# Power.net
KiCad netlist of a schematic drawn in Altium Designer
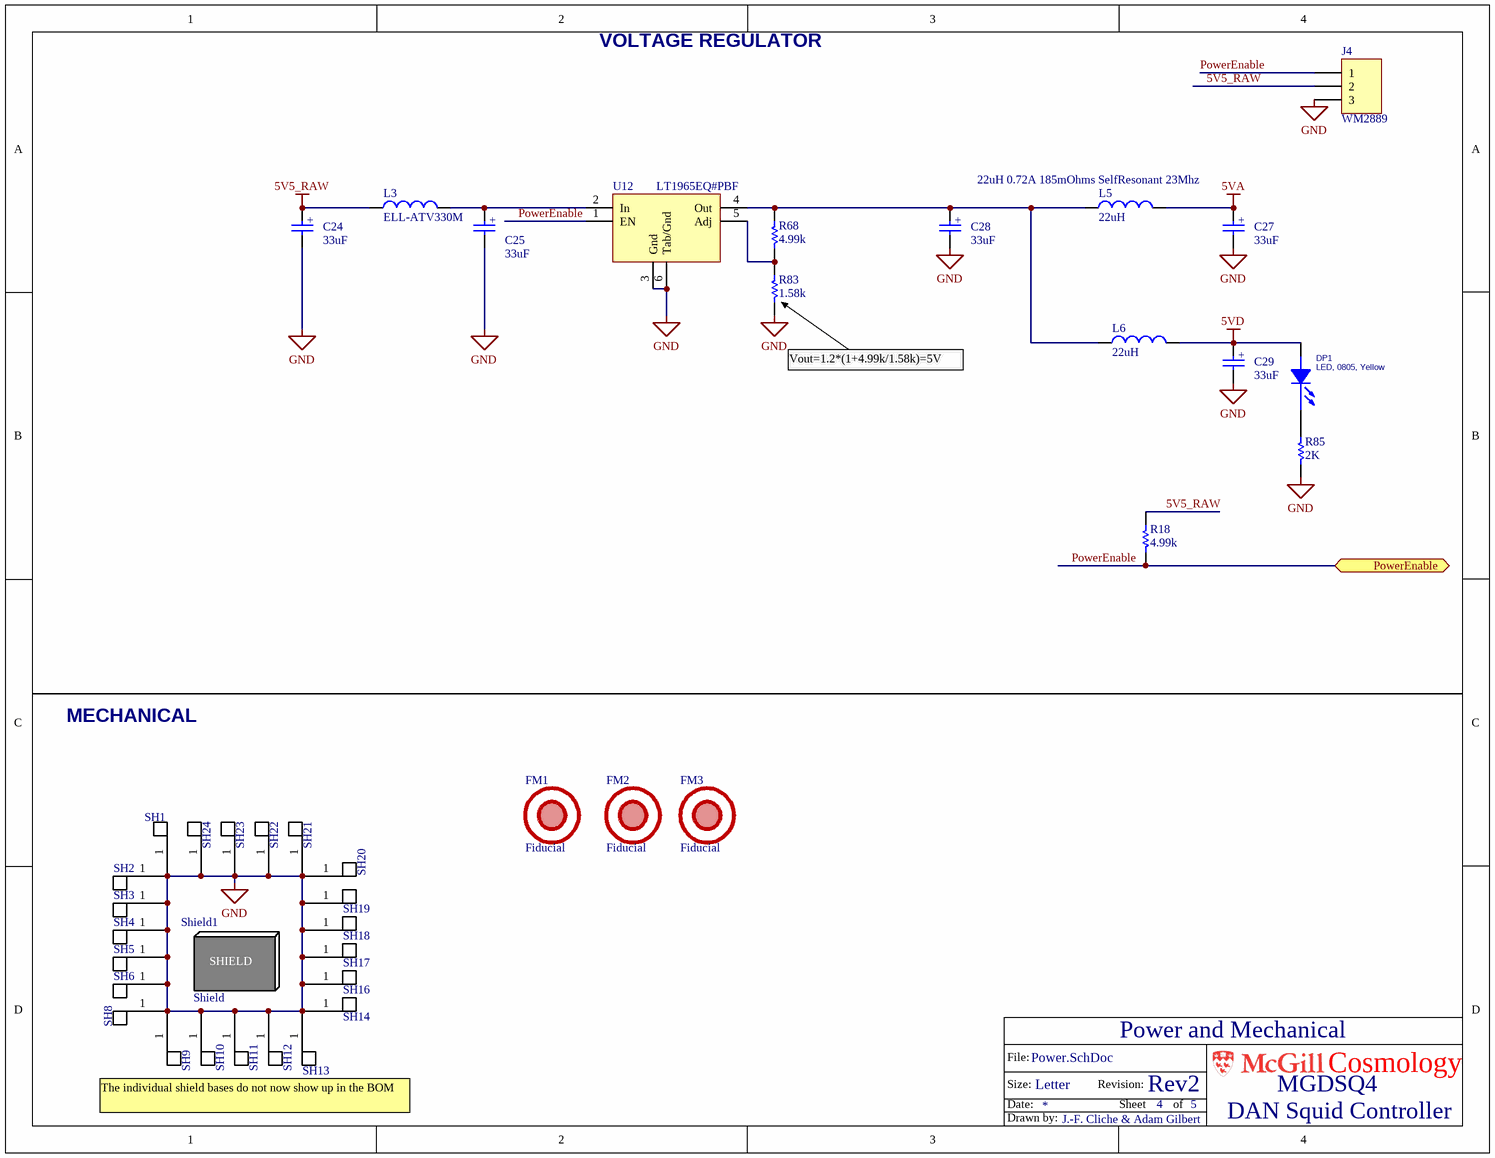
[diagram p0: Power.SchDoc]

(export (version "E")
  (design (tool "Eeschema 10.0.6"))
  (components
    (comp (ref "C24")
      (value "33uF")
      (footprint "TCASE-D")
      (description "CAP TANT CASE-D")
      (fields (field (name "VOLTAGE") "16V") (field (name "MANUFACTURER") "Generic"))
      (libsource (lib "MiniSquidCtrl") (part "Tantalum"))
    )
    (comp (ref "C25")
      (value "33uF")
      (footprint "TCASE-D")
      (description "CAP TANT CASE-D")
      (fields (field (name "VOLTAGE") "16V") (field (name "MANUFACTURER") "Generic"))
      (libsource (lib "MiniSquidCtrl") (part "Tantalum"))
    )
    (comp (ref "C27")
      (value "33uF")
      (footprint "TCASE-D")
      (description "CAP TANT CASE-D")
      (fields (field (name "VOLTAGE") "16V") (field (name "MANUFACTURER") "Generic"))
      (libsource (lib "MiniSquidCtrl") (part "Tantalum"))
    )
    (comp (ref "C28")
      (value "33uF")
      (footprint "TCASE-D")
      (description "CAP TANT CASE-D")
      (fields (field (name "VOLTAGE") "16V") (field (name "MANUFACTURER") "Generic"))
      (libsource (lib "MiniSquidCtrl") (part "Tantalum"))
    )
    (comp (ref "C29")
      (value "33uF")
      (footprint "TCASE-D")
      (description "CAP TANT CASE-D")
      (fields (field (name "VOLTAGE") "16V") (field (name "MANUFACTURER") "Generic"))
      (libsource (lib "MiniSquidCtrl") (part "Tantalum"))
    )
    (comp (ref "DP1")
      (value "LED, 0805, Yellow")
      (description "LED")
      (libsource (lib "MiniSquidCtrl") (part "LED, yellow, 0805, 2mA"))
    )
    (comp (ref "FM1")
      (value "Fiducial")
      (footprint "Fiducial_mark")
      (libsource (lib "MiniSquidCtrl") (part "Fiducial"))
    )
    (comp (ref "FM2")
      (value "Fiducial")
      (footprint "Fiducial_mark")
      (libsource (lib "MiniSquidCtrl") (part "Fiducial"))
    )
    (comp (ref "FM3")
      (value "Fiducial")
      (footprint "Fiducial_mark")
      (libsource (lib "MiniSquidCtrl") (part "Fiducial"))
    )
    (comp (ref "J4")
      (value "WM2889")
      (footprint "HDR1X3_MolexVertical")
      (description "3-Pin 0.1\" header")
      (fields (field (name "MANUFACTURER") "Digikey"))
      (libsource (lib "MiniSquidCtrl") (part "Header 3"))
    )
    (comp (ref "L3")
      (value "ELL-ATV330M")
      (footprint "ELLATV")
      (description "33uH 1.8A inductor 10mmx10mm")
      (fields (field (name "MANUFACTURER") "Panasonic - ECG") (field (name "TOLERANCE") "±20%"))
      (libsource (lib "MiniSquidCtrl") (part "ELL-ATV330M"))
    )
    (comp (ref "L5")
      (value "22uH")
      (footprint "SRR4028")
      (description "=PartConstraints")
      (fields
        (field (name "MANUFACTURER") "Bourns")
        (field (name "PARTCONSTRAINTS") "22uH 0.72A 185mOhms SelfResonant 23Mhz")
      )
      (libsource (lib "MiniSquidCtrl") (part "InductorSRR4028"))
    )
    (comp (ref "L6")
      (value "22uH")
      (footprint "SRR4028")
      (description "=PartConstraints")
      (fields (field (name "MANUFACTURER") "Bourns"))
      (libsource (lib "MiniSquidCtrl") (part "InductorSRR4028"))
    )
    (comp (ref "R18")
      (value "4.99k")
      (footprint "0603")
      (description "RES 0603")
      (fields (field (name "MANUFACTURER") "Generic"))
      (libsource (lib "MiniSquidCtrl") (part "Res0603"))
    )
    (comp (ref "R68")
      (value "4.99k")
      (footprint "0603")
      (description "RES 0603")
      (fields (field (name "MANUFACTURER") "Generic"))
      (libsource (lib "MiniSquidCtrl") (part "Res0603"))
    )
    (comp (ref "R83")
      (value "1.58k")
      (footprint "0603")
      (description "RES 0603")
      (fields (field (name "MANUFACTURER") "Generic"))
      (libsource (lib "MiniSquidCtrl") (part "Res0603"))
    )
    (comp (ref "R85")
      (value "2K")
      (footprint "0603")
      (description "RES 0603")
      (fields (field (name "MANUFACTURER") "Generic") (field (name "Comment") "2k"))
      (libsource (lib "MiniSquidCtrl") (part "Res0603"))
    )
    (comp (ref "SH1")
      (value "LeaderTech 20S-CBS-2x0.5x0.2 - DIVIDE QUANITY REQURIED BY 10!")
      (footprint "SHIELD BASE CORNER")
      (fields (field (name "MANUFACTURER") "LeaderTech"))
      (libsource (lib "MiniSquidCtrl") (part "ShieldBase"))
    )
    (comp (ref "SH2")
      (value "LeaderTech 20S-CBS-2x0.5x0.2 - DIVIDE QUANITY REQURIED BY 10!")
      (footprint "SHIELD BASE")
      (fields (field (name "MANUFACTURER") "LeaderTech"))
      (libsource (lib "MiniSquidCtrl") (part "ShieldBase"))
    )
    (comp (ref "SH3")
      (value "LeaderTech 20S-CBS-2x0.5x0.2 - DIVIDE QUANITY REQURIED BY 10!")
      (footprint "SHIELD BASE")
      (fields (field (name "MANUFACTURER") "LeaderTech"))
      (libsource (lib "MiniSquidCtrl") (part "ShieldBase"))
    )
    (comp (ref "SH4")
      (value "LeaderTech 20S-CBS-2x0.5x0.2 - DIVIDE QUANITY REQURIED BY 10!")
      (footprint "SHIELD BASE")
      (fields (field (name "MANUFACTURER") "LeaderTech"))
      (libsource (lib "MiniSquidCtrl") (part "ShieldBase"))
    )
    (comp (ref "SH5")
      (value "LeaderTech 20S-CBS-2x0.5x0.2 - DIVIDE QUANITY REQURIED BY 10!")
      (footprint "SHIELD BASE")
      (fields (field (name "MANUFACTURER") "LeaderTech"))
      (libsource (lib "MiniSquidCtrl") (part "ShieldBase"))
    )
    (comp (ref "SH6")
      (value "LeaderTech 20S-CBS-2x0.5x0.2 - DIVIDE QUANITY REQURIED BY 10!")
      (footprint "SHIELD BASE")
      (fields (field (name "MANUFACTURER") "LeaderTech"))
      (libsource (lib "MiniSquidCtrl") (part "ShieldBase"))
    )
    (comp (ref "SH8")
      (value "LeaderTech 20S-CBS-2x0.5x0.2 - DIVIDE QUANITY REQURIED BY 10!")
      (footprint "SHIELD BASE CORNER")
      (fields (field (name "MANUFACTURER") "LeaderTech"))
      (libsource (lib "MiniSquidCtrl") (part "ShieldBase"))
    )
    (comp (ref "SH9")
      (value "LeaderTech 20S-CBS-2x0.5x0.2 - DIVIDE QUANITY REQURIED BY 10!")
      (footprint "SHIELD BASE")
      (fields (field (name "MANUFACTURER") "LeaderTech"))
      (libsource (lib "MiniSquidCtrl") (part "ShieldBase"))
    )
    (comp (ref "SH10")
      (value "LeaderTech 20S-CBS-2x0.5x0.2 - DIVIDE QUANITY REQURIED BY 10!")
      (footprint "SHIELD BASE")
      (fields (field (name "MANUFACTURER") "LeaderTech"))
      (libsource (lib "MiniSquidCtrl") (part "ShieldBase"))
    )
    (comp (ref "SH11")
      (value "LeaderTech 20S-CBS-2x0.5x0.2 - DIVIDE QUANITY REQURIED BY 10!")
      (footprint "SHIELD BASE")
      (fields (field (name "MANUFACTURER") "LeaderTech"))
      (libsource (lib "MiniSquidCtrl") (part "ShieldBase"))
    )
    (comp (ref "SH12")
      (value "LeaderTech 20S-CBS-2x0.5x0.2 - DIVIDE QUANITY REQURIED BY 10!")
      (footprint "SHIELD BASE")
      (fields (field (name "MANUFACTURER") "LeaderTech"))
      (libsource (lib "MiniSquidCtrl") (part "ShieldBase"))
    )
    (comp (ref "SH13")
      (value "LeaderTech 20S-CBS-2x0.5x0.2 - DIVIDE QUANITY REQURIED BY 10!")
      (footprint "SHIELD BASE CORNER")
      (fields (field (name "MANUFACTURER") "LeaderTech"))
      (libsource (lib "MiniSquidCtrl") (part "ShieldBase"))
    )
    (comp (ref "SH14")
      (value "LeaderTech 20S-CBS-2x0.5x0.2 - DIVIDE QUANITY REQURIED BY 10!")
      (footprint "SHIELD BASE")
      (fields (field (name "MANUFACTURER") "LeaderTech"))
      (libsource (lib "MiniSquidCtrl") (part "ShieldBase"))
    )
    (comp (ref "SH16")
      (value "LeaderTech 20S-CBS-2x0.5x0.2 - DIVIDE QUANITY REQURIED BY 10!")
      (footprint "SHIELD BASE")
      (fields (field (name "MANUFACTURER") "LeaderTech"))
      (libsource (lib "MiniSquidCtrl") (part "ShieldBase"))
    )
    (comp (ref "SH17")
      (value "LeaderTech 20S-CBS-2x0.5x0.2 - DIVIDE QUANITY REQURIED BY 10!")
      (footprint "SHIELD BASE")
      (fields (field (name "MANUFACTURER") "LeaderTech"))
      (libsource (lib "MiniSquidCtrl") (part "ShieldBase"))
    )
    (comp (ref "SH18")
      (value "LeaderTech 20S-CBS-2x0.5x0.2 - DIVIDE QUANITY REQURIED BY 10!")
      (footprint "SHIELD BASE")
      (fields (field (name "MANUFACTURER") "LeaderTech"))
      (libsource (lib "MiniSquidCtrl") (part "ShieldBase"))
    )
    (comp (ref "SH19")
      (value "LeaderTech 20S-CBS-2x0.5x0.2 - DIVIDE QUANITY REQURIED BY 10!")
      (footprint "SHIELD BASE")
      (fields (field (name "MANUFACTURER") "LeaderTech"))
      (libsource (lib "MiniSquidCtrl") (part "ShieldBase"))
    )
    (comp (ref "SH20")
      (value "LeaderTech 20S-CBS-2x0.5x0.2 - DIVIDE QUANITY REQURIED BY 10!")
      (footprint "SHIELD BASE CORNER")
      (fields (field (name "MANUFACTURER") "LeaderTech"))
      (libsource (lib "MiniSquidCtrl") (part "ShieldBase"))
    )
    (comp (ref "SH21")
      (value "LeaderTech 20S-CBS-2x0.5x0.2 - DIVIDE QUANITY REQURIED BY 10!")
      (footprint "SHIELD BASE")
      (fields (field (name "MANUFACTURER") "LeaderTech"))
      (libsource (lib "MiniSquidCtrl") (part "ShieldBase"))
    )
    (comp (ref "SH22")
      (value "LeaderTech 20S-CBS-2x0.5x0.2 - DIVIDE QUANITY REQURIED BY 10!")
      (footprint "SHIELD BASE")
      (fields (field (name "MANUFACTURER") "LeaderTech"))
      (libsource (lib "MiniSquidCtrl") (part "ShieldBase"))
    )
    (comp (ref "SH23")
      (value "LeaderTech 20S-CBS-2x0.5x0.2 - DIVIDE QUANITY REQURIED BY 10!")
      (footprint "SHIELD BASE")
      (fields (field (name "MANUFACTURER") "LeaderTech"))
      (libsource (lib "MiniSquidCtrl") (part "ShieldBase"))
    )
    (comp (ref "SH24")
      (value "LeaderTech 20S-CBS-2x0.5x0.2 - DIVIDE QUANITY REQURIED BY 10!")
      (footprint "SHIELD BASE")
      (fields (field (name "MANUFACTURER") "LeaderTech"))
      (libsource (lib "MiniSquidCtrl") (part "ShieldBase"))
    )
    (comp (ref "Shield1")
      (value "Shield")
      (description "20S-CBSA-3x2.5x0.2 (assembled fence and cover)")
      (fields (field (name "MANUFACTURER") "Leadertech"))
      (libsource (lib "MiniSquidCtrl") (part "SHIELD 20S-CBS-3x2.5x0.2"))
    )
    (comp (ref "U12")
      (value "LT1965EQ#PBF")
      (footprint "D2-PAK-6_LT3080")
      (description "Low dropout regulator, single resistor, 1.1A")
      (libsource (lib "MiniSquidCtrl") (part "LT1965EQ"))
    )
  )
  (nets
    (net (code "1") (name "/PowerEnable") (class "Default")
      (node (ref "J4") (pin "1") (pinfunction "1_1") (pintype "passive"))
      (node (ref "R18") (pin "1") (pinfunction "1_1") (pintype "passive"))
      (node (ref "U12") (pin "1") (pinfunction "EN_1") (pintype "power_in"))
    )
    (net (code "2") (name "5V5_RAW") (class "Default")
      (node (ref "C24") (pin "1") (pinfunction "1_1") (pintype "passive"))
      (node (ref "J4") (pin "2") (pinfunction "2_2") (pintype "passive"))
      (node (ref "L3") (pin "1") (pinfunction "1_1") (pintype "passive"))
      (node (ref "R18") (pin "2") (pinfunction "2_2") (pintype "passive"))
    )
    (net (code "3") (name "5VA") (class "Default")
      (node (ref "C27") (pin "1") (pinfunction "1_1") (pintype "passive"))
      (node (ref "L5") (pin "2") (pinfunction "2_2") (pintype "passive"))
    )
    (net (code "4") (name "5VD") (class "Default")
      (node (ref "C29") (pin "1") (pinfunction "1_1") (pintype "passive"))
      (node (ref "DP1") (pin "1") (pinfunction "ANODE_1") (pintype "passive"))
      (node (ref "L6") (pin "2") (pinfunction "2_2") (pintype "passive"))
    )
    (net (code "5") (name "GND") (class "Default")
      (node (ref "C24") (pin "2") (pinfunction "2_2") (pintype "passive"))
      (node (ref "C25") (pin "2") (pinfunction "2_2") (pintype "passive"))
      (node (ref "C27") (pin "2") (pinfunction "2_2") (pintype "passive"))
      (node (ref "C28") (pin "2") (pinfunction "2_2") (pintype "passive"))
      (node (ref "C29") (pin "2") (pinfunction "2_2") (pintype "passive"))
      (node (ref "J4") (pin "3") (pinfunction "3_3") (pintype "passive"))
      (node (ref "R83") (pin "1") (pinfunction "1_1") (pintype "passive"))
      (node (ref "R85") (pin "2") (pinfunction "2_2") (pintype "passive"))
      (node (ref "SH1") (pin "1") (pinfunction "1_1") (pintype "passive"))
      (node (ref "SH10") (pin "1") (pinfunction "1_1") (pintype "passive"))
      (node (ref "SH11") (pin "1") (pinfunction "1_1") (pintype "passive"))
      (node (ref "SH12") (pin "1") (pinfunction "1_1") (pintype "passive"))
      (node (ref "SH13") (pin "1") (pinfunction "1_1") (pintype "passive"))
      (node (ref "SH14") (pin "1") (pinfunction "1_1") (pintype "passive"))
      (node (ref "SH16") (pin "1") (pinfunction "1_1") (pintype "passive"))
      (node (ref "SH17") (pin "1") (pinfunction "1_1") (pintype "passive"))
      (node (ref "SH18") (pin "1") (pinfunction "1_1") (pintype "passive"))
      (node (ref "SH19") (pin "1") (pinfunction "1_1") (pintype "passive"))
      (node (ref "SH2") (pin "1") (pinfunction "1_1") (pintype "passive"))
      (node (ref "SH20") (pin "1") (pinfunction "1_1") (pintype "passive"))
      (node (ref "SH21") (pin "1") (pinfunction "1_1") (pintype "passive"))
      (node (ref "SH22") (pin "1") (pinfunction "1_1") (pintype "passive"))
      (node (ref "SH23") (pin "1") (pinfunction "1_1") (pintype "passive"))
      (node (ref "SH24") (pin "1") (pinfunction "1_1") (pintype "passive"))
      (node (ref "SH3") (pin "1") (pinfunction "1_1") (pintype "passive"))
      (node (ref "SH4") (pin "1") (pinfunction "1_1") (pintype "passive"))
      (node (ref "SH5") (pin "1") (pinfunction "1_1") (pintype "passive"))
      (node (ref "SH6") (pin "1") (pinfunction "1_1") (pintype "passive"))
      (node (ref "SH8") (pin "1") (pinfunction "1_1") (pintype "passive"))
      (node (ref "SH9") (pin "1") (pinfunction "1_1") (pintype "passive"))
      (node (ref "U12") (pin "3") (pinfunction "Gnd_3") (pintype "power_in"))
      (node (ref "U12") (pin "6") (pinfunction "Tab/Gnd_6") (pintype "power_in"))
    )
    (net (code "6") (name "Net-(DP1-CATHODE)") (class "Default")
      (node (ref "DP1") (pin "2") (pinfunction "CATHODE_2") (pintype "passive"))
      (node (ref "R85") (pin "1") (pinfunction "1_1") (pintype "passive"))
    )
    (net (code "7") (name "Net-(U12-Adj)") (class "Default")
      (node (ref "R68") (pin "1") (pinfunction "1_1") (pintype "passive"))
      (node (ref "R83") (pin "2") (pinfunction "2_2") (pintype "passive"))
      (node (ref "U12") (pin "5") (pinfunction "Adj_5") (pintype "power_in"))
    )
    (net (code "8") (name "Net-(U12-In)") (class "Default")
      (node (ref "C25") (pin "1") (pinfunction "1_1") (pintype "passive"))
      (node (ref "L3") (pin "2") (pinfunction "2_2") (pintype "passive"))
      (node (ref "U12") (pin "2") (pinfunction "In_2") (pintype "power_in"))
    )
    (net (code "9") (name "Net-(U12-Out)") (class "Default")
      (node (ref "C28") (pin "1") (pinfunction "1_1") (pintype "passive"))
      (node (ref "L5") (pin "1") (pinfunction "1_1") (pintype "passive"))
      (node (ref "L6") (pin "1") (pinfunction "1_1") (pintype "passive"))
      (node (ref "R68") (pin "2") (pinfunction "2_2") (pintype "passive"))
      (node (ref "U12") (pin "4") (pinfunction "Out_4") (pintype "power_in"))
    )
  )
)
